# Isolation_Unit.net
KiCad netlist of a schematic drawn in Altium Designer
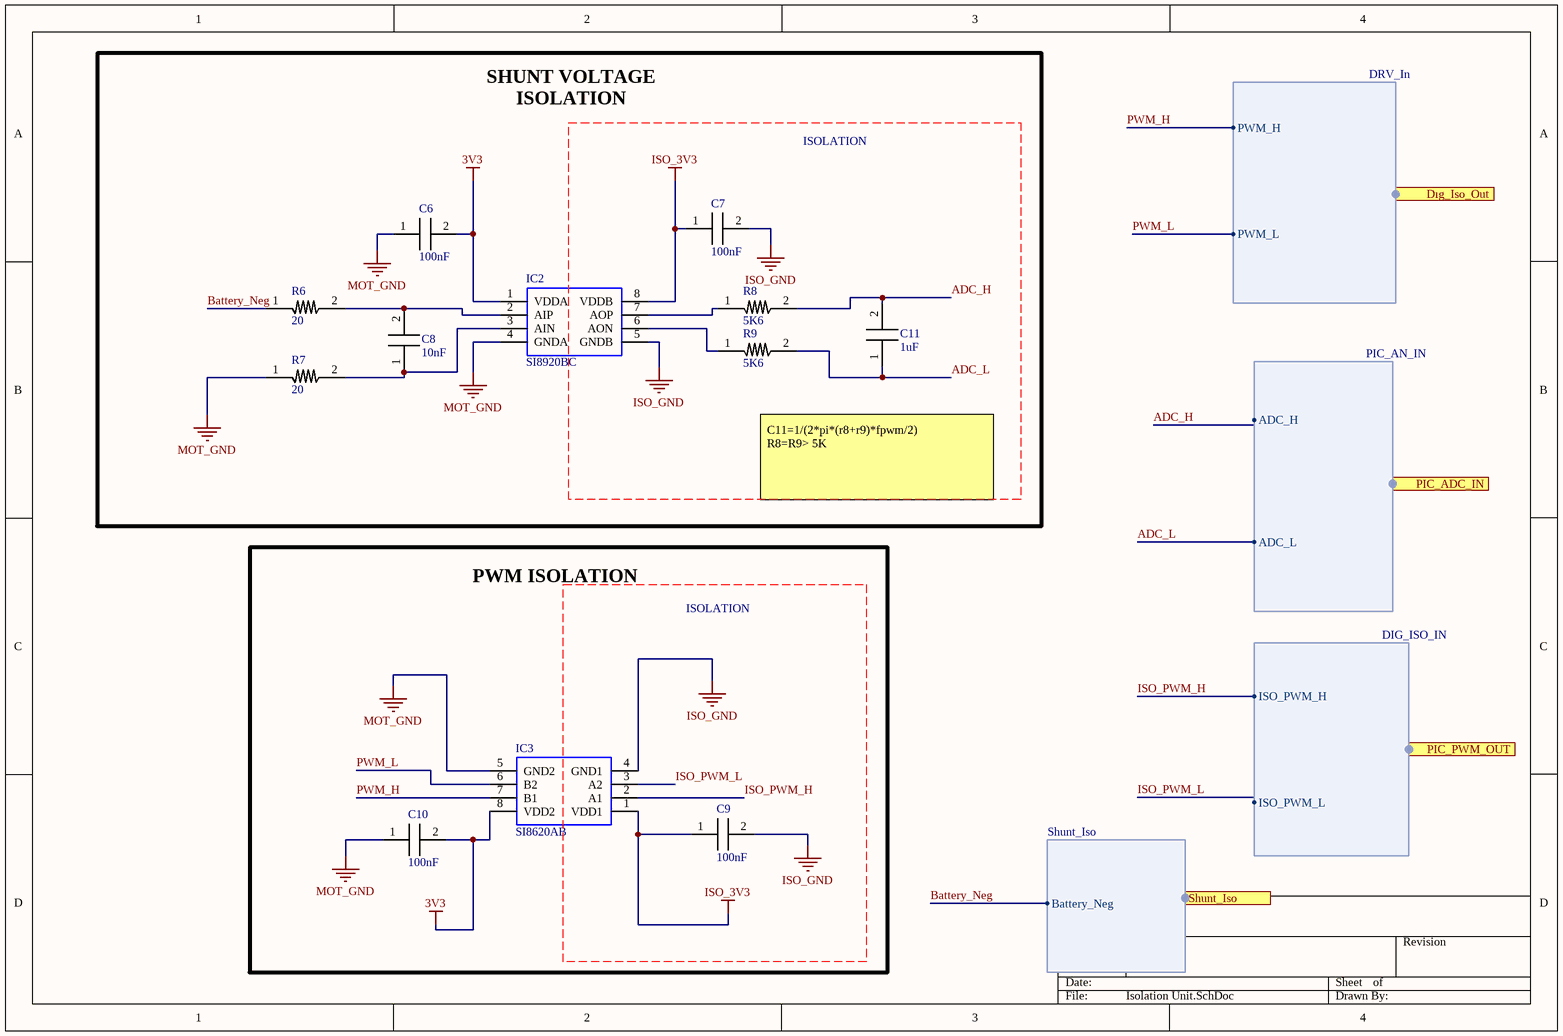
[diagram p0: Isolation Unit.SchDoc]

(export (version "E")
  (design (tool "Eeschema 10.0.6"))
  (components
    (comp (ref "C6")
      (value "CAP 100nF")
      (footprint "0603_CAP")
      (fields (field (name "PARAMETER 1") "100nF"))
      (libsource (lib "Schlib1") (part "CAP 100nF"))
    )
    (comp (ref "C7")
      (value "CAP 100nF")
      (footprint "0603_CAP")
      (fields (field (name "PARAMETER 1") "100nF"))
      (libsource (lib "Schlib1") (part "CAP 100nF"))
    )
    (comp (ref "C8")
      (value "CAP 10nF")
      (footprint "0603_CAP")
      (fields (field (name "PARAMETER 1") "10nF"))
      (libsource (lib "Schlib1") (part "CAP 10nF"))
    )
    (comp (ref "C9")
      (value "CAP 100nF")
      (footprint "0603_CAP")
      (fields (field (name "PARAMETER 1") "100nF"))
      (libsource (lib "Schlib1") (part "CAP 100nF"))
    )
    (comp (ref "C10")
      (value "CAP 100nF")
      (footprint "0603_CAP")
      (fields (field (name "PARAMETER 1") "100nF"))
      (libsource (lib "Schlib1") (part "CAP 100nF"))
    )
    (comp (ref "C11")
      (value "CAP 1uF")
      (footprint "0603_CAP")
      (fields (field (name "PARAMETER 1") "1uF"))
      (libsource (lib "Schlib1") (part "CAP 1uF"))
    )
    (comp (ref "IC2")
      (value "SI8920BC")
      (footprint "SI8920BC-IP")
      (libsource (lib "Schlib1") (part "IC ISO OP-AMP,SI8920BC"))
    )
    (comp (ref "IC3")
      (value "SI8620AB")
      (footprint "SI8620AB")
      (libsource (lib "Schlib1") (part "IC ISO DIG, SI8620AB"))
    )
    (comp (ref "R6")
      (value "RES, 20, 0603")
      (footprint "0603_RES")
      (fields (field (name "PARAMETER 1") "20"))
      (libsource (lib "Schlib1") (part "RES, 20, 0603"))
    )
    (comp (ref "R7")
      (value "RES, 20, 0603")
      (footprint "0603_RES")
      (fields (field (name "PARAMETER 1") "20"))
      (libsource (lib "Schlib1") (part "RES, 20, 0603"))
    )
    (comp (ref "R8")
      (value "RES, 5K6, 0603")
      (footprint "0603_RES")
      (fields (field (name "PARAMETER 1") "5K6"))
      (libsource (lib "Schlib1") (part "RES, 5K6, 0603"))
    )
    (comp (ref "R9")
      (value "RES, 5K6, 0603")
      (footprint "0603_RES")
      (fields (field (name "PARAMETER 1") "5K6"))
      (libsource (lib "Schlib1") (part "RES, 5K6, 0603"))
    )
  )
  (nets
    (net (code "5") (name "/ADC_H") (class "Default")
      (node (ref "C11") (pin "2") (pinfunction "2_2") (pintype "passive"))
      (node (ref "R8") (pin "2") (pinfunction "2_2") (pintype "passive"))
    )
    (net (code "6") (name "/ADC_L") (class "Default")
      (node (ref "C11") (pin "1") (pinfunction "1_1") (pintype "passive"))
      (node (ref "R9") (pin "2") (pinfunction "2_2") (pintype "passive"))
    )
    (net (code "7") (name "/Battery_Neg") (class "Default")
      (node (ref "R6") (pin "1") (pinfunction "1_1") (pintype "passive"))
    )
    (net (code "8") (name "/ISO_PWM_H") (class "Default")
      (node (ref "IC3") (pin "2") (pinfunction "A1_2") (pintype "passive"))
    )
    (net (code "9") (name "/ISO_PWM_L") (class "Default")
      (node (ref "IC3") (pin "3") (pinfunction "A2_3") (pintype "passive"))
    )
    (net (code "10") (name "/PWM_H") (class "Default")
      (node (ref "IC3") (pin "7") (pinfunction "B1_7") (pintype "passive"))
    )
    (net (code "11") (name "/PWM_L") (class "Default")
      (node (ref "IC3") (pin "6") (pinfunction "B2_6") (pintype "passive"))
    )
    (net (code "16") (name "3V3") (class "Default")
      (node (ref "C10") (pin "2") (pinfunction "2_2") (pintype "passive"))
      (node (ref "C6") (pin "2") (pinfunction "2_2") (pintype "passive"))
      (node (ref "IC2") (pin "1") (pinfunction "VDDA_1") (pintype "power_in"))
      (node (ref "IC3") (pin "8") (pinfunction "VDD2_8") (pintype "power_in"))
    )
    (net (code "17") (name "ISO_3V3") (class "Default")
      (node (ref "C7") (pin "1") (pinfunction "1_1") (pintype "passive"))
      (node (ref "C9") (pin "1") (pinfunction "1_1") (pintype "passive"))
      (node (ref "IC2") (pin "8") (pinfunction "VDDB_8") (pintype "power_in"))
      (node (ref "IC3") (pin "1") (pinfunction "VDD1_1") (pintype "power_in"))
    )
    (net (code "18") (name "ISO_GND") (class "Default")
      (node (ref "C7") (pin "2") (pinfunction "2_2") (pintype "passive"))
      (node (ref "C9") (pin "2") (pinfunction "2_2") (pintype "passive"))
      (node (ref "IC2") (pin "5") (pinfunction "GNDB_5") (pintype "passive"))
      (node (ref "IC3") (pin "4") (pinfunction "GND1_4") (pintype "passive"))
    )
    (net (code "19") (name "MOT_GND") (class "Default")
      (node (ref "C10") (pin "1") (pinfunction "1_1") (pintype "passive"))
      (node (ref "C6") (pin "1") (pinfunction "1_1") (pintype "passive"))
      (node (ref "IC2") (pin "4") (pinfunction "GNDA_4") (pintype "passive"))
      (node (ref "IC3") (pin "5") (pinfunction "GND2_5") (pintype "passive"))
      (node (ref "R7") (pin "1") (pinfunction "1_1") (pintype "passive"))
    )
    (net (code "20") (name "Net-(IC2-AIN)") (class "Default")
      (node (ref "C8") (pin "1") (pinfunction "1_1") (pintype "passive"))
      (node (ref "IC2") (pin "3") (pinfunction "AIN_3") (pintype "passive"))
      (node (ref "R7") (pin "2") (pinfunction "2_2") (pintype "passive"))
    )
    (net (code "21") (name "Net-(IC2-AIP)") (class "Default")
      (node (ref "C8") (pin "2") (pinfunction "2_2") (pintype "passive"))
      (node (ref "IC2") (pin "2") (pinfunction "AIP_2") (pintype "passive"))
      (node (ref "R6") (pin "2") (pinfunction "2_2") (pintype "passive"))
    )
    (net (code "22") (name "Net-(IC2-AON)") (class "Default")
      (node (ref "IC2") (pin "6") (pinfunction "AON_6") (pintype "passive"))
      (node (ref "R9") (pin "1") (pinfunction "1_1") (pintype "passive"))
    )
    (net (code "23") (name "Net-(IC2-AOP)") (class "Default")
      (node (ref "IC2") (pin "7") (pinfunction "AOP_7") (pintype "passive"))
      (node (ref "R8") (pin "1") (pinfunction "1_1") (pintype "passive"))
    )
  )
)
